# Microcontroller_board_Photodiode_plate.net
KiCad netlist of a schematic drawn in EasyEDA
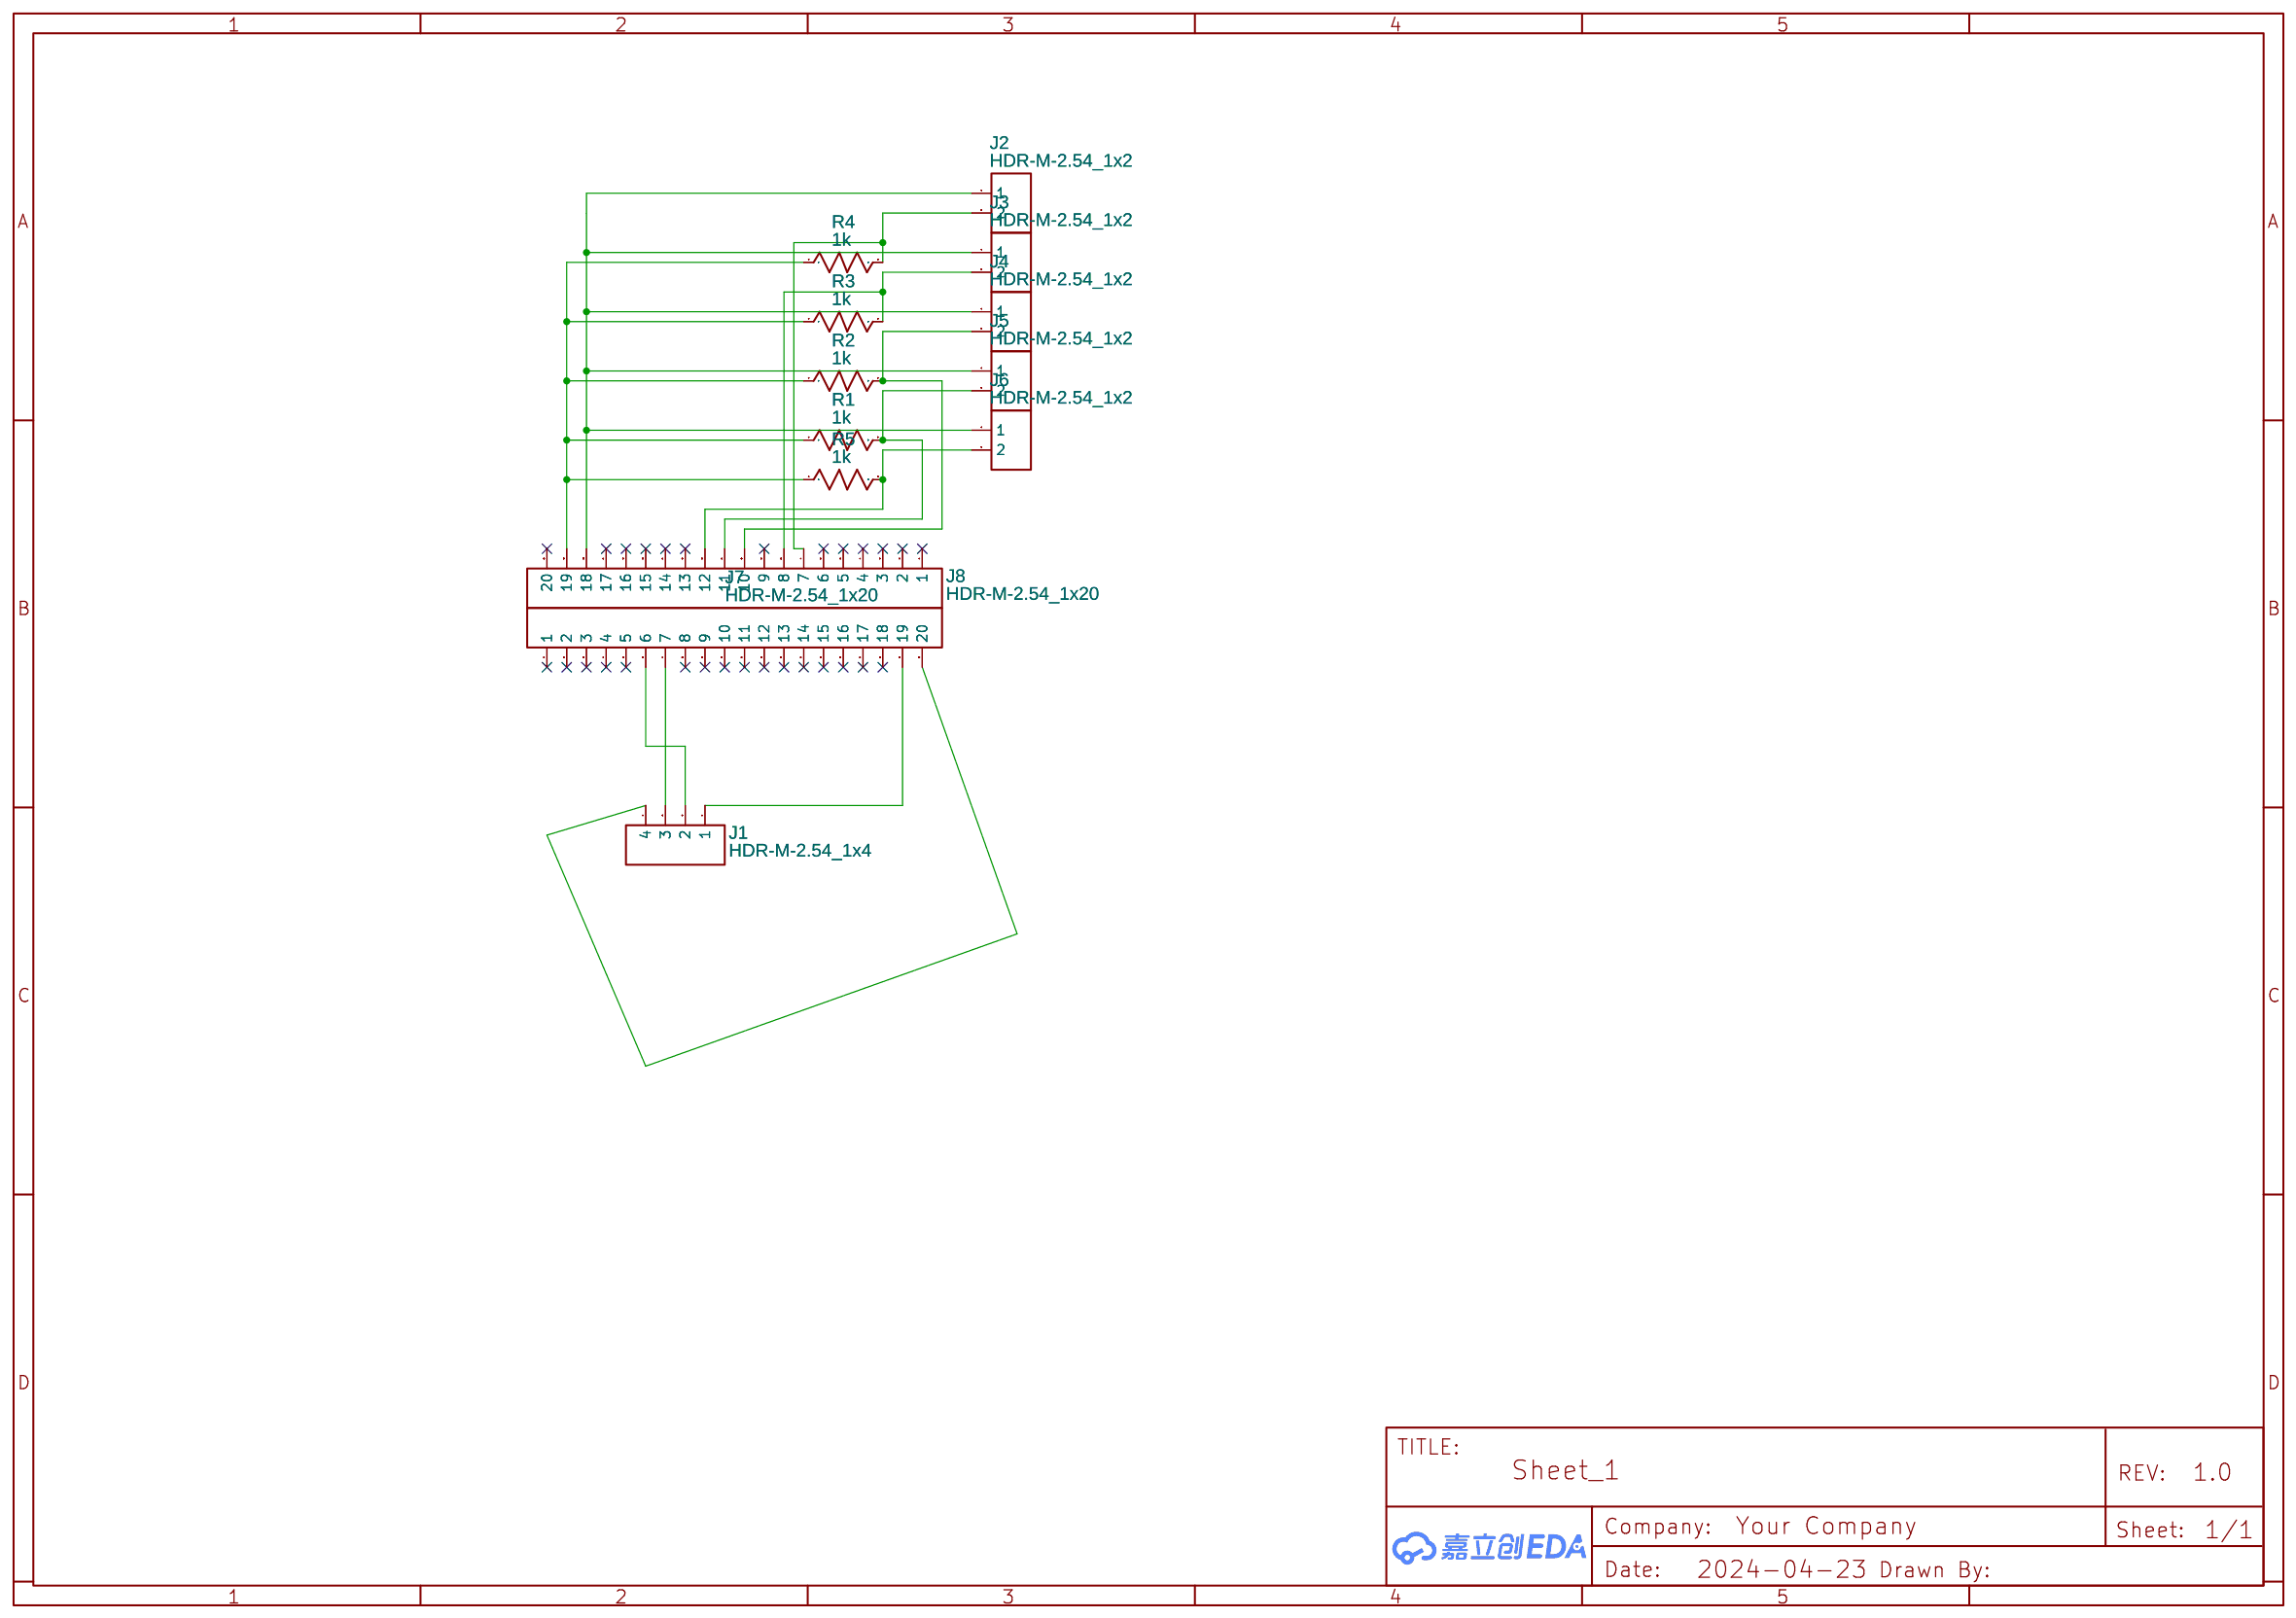
[diagram p0: schematic sheet]

(export (version "E")
  (design (tool "Eeschema 10.0.6"))
  (components
    (comp (ref "J1")
      (value "HDR-M-2.54_1x4")
      (fields (field (name "BOM_Supplier Part") "C124378"))
      (libsource (lib "") (part "HDR-M-2.54_1x4"))
    )
    (comp (ref "J2")
      (value "HDR-M-2.54_1x2")
      (fields (field (name "BOM_Supplier Part") "C124375"))
      (libsource (lib "") (part "HDR-M-2.54_1x2"))
    )
    (comp (ref "J3")
      (value "HDR-M-2.54_1x2")
      (fields (field (name "BOM_Supplier Part") "C124375"))
      (libsource (lib "") (part "HDR-M-2.54_1x2"))
    )
    (comp (ref "J4")
      (value "HDR-M-2.54_1x2")
      (fields (field (name "BOM_Supplier Part") "C124375"))
      (libsource (lib "") (part "HDR-M-2.54_1x2"))
    )
    (comp (ref "J5")
      (value "HDR-M-2.54_1x2")
      (fields (field (name "BOM_Supplier Part") "C124375"))
      (libsource (lib "") (part "HDR-M-2.54_1x2"))
    )
    (comp (ref "J6")
      (value "HDR-M-2.54_1x2")
      (fields (field (name "BOM_Supplier Part") "C124375"))
      (libsource (lib "") (part "HDR-M-2.54_1x2"))
    )
    (comp (ref "J7")
      (value "HDR-M-2.54_1x20")
      (fields (field (name "BOM_Supplier Part") "C50981"))
      (libsource (lib "") (part "HDR-M-2.54_1x20"))
    )
    (comp (ref "J8")
      (value "HDR-M-2.54_1x20")
      (fields (field (name "BOM_Supplier Part") "C50981"))
      (libsource (lib "") (part "HDR-M-2.54_1x20_1"))
    )
    (comp (ref "R1") (value "1k") (libsource (lib "") (part "R_AXIAL-0.4_US")))
    (comp (ref "R2") (value "1k") (libsource (lib "") (part "R_AXIAL-0.4_US")))
    (comp (ref "R3") (value "1k") (libsource (lib "") (part "R_AXIAL-0.4_US")))
    (comp (ref "R4") (value "1k") (libsource (lib "") (part "R_AXIAL-0.4_US")))
    (comp (ref "R5") (value "1k") (libsource (lib "") (part "R_AXIAL-0.4_US")))
  )
  (nets
    (net (code "1") (name "Net-(J1-Pad1)") (class "Default")
      (node (ref "J1") (pin "1") (pinfunction "1_1") (pintype "unspecified"))
      (node (ref "J7") (pin "19") (pinfunction "19_19") (pintype "unspecified"))
    )
    (net (code "2") (name "Net-(J1-Pad2)") (class "Default")
      (node (ref "J1") (pin "2") (pinfunction "2_2") (pintype "unspecified"))
      (node (ref "J7") (pin "6") (pinfunction "6_6") (pintype "unspecified"))
    )
    (net (code "3") (name "Net-(J1-Pad3)") (class "Default")
      (node (ref "J1") (pin "3") (pinfunction "3_3") (pintype "unspecified"))
      (node (ref "J7") (pin "7") (pinfunction "7_7") (pintype "unspecified"))
    )
    (net (code "4") (name "Net-(J1-Pad4)") (class "Default")
      (node (ref "J1") (pin "4") (pinfunction "4_4") (pintype "unspecified"))
      (node (ref "J7") (pin "20") (pinfunction "20_20") (pintype "unspecified"))
    )
    (net (code "5") (name "Net-(J2-Pad1)") (class "Default")
      (node (ref "J2") (pin "1") (pinfunction "1_1") (pintype "unspecified"))
      (node (ref "J3") (pin "1") (pinfunction "1_1") (pintype "unspecified"))
      (node (ref "J4") (pin "1") (pinfunction "1_1") (pintype "unspecified"))
      (node (ref "J5") (pin "1") (pinfunction "1_1") (pintype "unspecified"))
      (node (ref "J6") (pin "1") (pinfunction "1_1") (pintype "unspecified"))
      (node (ref "J8") (pin "18") (pinfunction "18_18") (pintype "unspecified"))
    )
    (net (code "6") (name "Net-(J2-Pad2)") (class "Default")
      (node (ref "J2") (pin "2") (pinfunction "2_2") (pintype "unspecified"))
      (node (ref "J8") (pin "7") (pinfunction "7_7") (pintype "unspecified"))
      (node (ref "R4") (pin "2") (pinfunction "2_2") (pintype "unspecified"))
    )
    (net (code "7") (name "Net-(J3-Pad2)") (class "Default")
      (node (ref "J3") (pin "2") (pinfunction "2_2") (pintype "unspecified"))
      (node (ref "J8") (pin "8") (pinfunction "8_8") (pintype "unspecified"))
      (node (ref "R3") (pin "2") (pinfunction "2_2") (pintype "unspecified"))
    )
    (net (code "8") (name "Net-(J4-Pad2)") (class "Default")
      (node (ref "J4") (pin "2") (pinfunction "2_2") (pintype "unspecified"))
      (node (ref "J8") (pin "10") (pinfunction "10_10") (pintype "unspecified"))
      (node (ref "R2") (pin "2") (pinfunction "2_2") (pintype "unspecified"))
    )
    (net (code "9") (name "Net-(J5-Pad2)") (class "Default")
      (node (ref "J5") (pin "2") (pinfunction "2_2") (pintype "unspecified"))
      (node (ref "J8") (pin "11") (pinfunction "11_11") (pintype "unspecified"))
      (node (ref "R1") (pin "2") (pinfunction "2_2") (pintype "unspecified"))
    )
    (net (code "10") (name "Net-(J6-Pad2)") (class "Default")
      (node (ref "J6") (pin "2") (pinfunction "2_2") (pintype "unspecified"))
      (node (ref "J8") (pin "12") (pinfunction "12_12") (pintype "unspecified"))
      (node (ref "R5") (pin "2") (pinfunction "2_2") (pintype "unspecified"))
    )
    (net (code "11") (name "Net-(J8-Pad19)") (class "Default")
      (node (ref "J8") (pin "19") (pinfunction "19_19") (pintype "unspecified"))
      (node (ref "R1") (pin "1") (pinfunction "1_1") (pintype "unspecified"))
      (node (ref "R2") (pin "1") (pinfunction "1_1") (pintype "unspecified"))
      (node (ref "R3") (pin "1") (pinfunction "1_1") (pintype "unspecified"))
      (node (ref "R4") (pin "1") (pinfunction "1_1") (pintype "unspecified"))
      (node (ref "R5") (pin "1") (pinfunction "1_1") (pintype "unspecified"))
    )
    (net (code "12") (name "unconnected-(J7-Pad1)") (class "Default")
      (node (ref "J7") (pin "1") (pinfunction "1_1") (pintype "unspecified+no_connect"))
    )
    (net (code "13") (name "unconnected-(J7-Pad2)") (class "Default")
      (node (ref "J7") (pin "2") (pinfunction "2_2") (pintype "unspecified+no_connect"))
    )
    (net (code "14") (name "unconnected-(J7-Pad3)") (class "Default")
      (node (ref "J7") (pin "3") (pinfunction "3_3") (pintype "unspecified+no_connect"))
    )
    (net (code "15") (name "unconnected-(J7-Pad4)") (class "Default")
      (node (ref "J7") (pin "4") (pinfunction "4_4") (pintype "unspecified+no_connect"))
    )
    (net (code "16") (name "unconnected-(J7-Pad5)") (class "Default")
      (node (ref "J7") (pin "5") (pinfunction "5_5") (pintype "unspecified+no_connect"))
    )
    (net (code "17") (name "unconnected-(J7-Pad8)") (class "Default")
      (node (ref "J7") (pin "8") (pinfunction "8_8") (pintype "unspecified+no_connect"))
    )
    (net (code "18") (name "unconnected-(J7-Pad9)") (class "Default")
      (node (ref "J7") (pin "9") (pinfunction "9_9") (pintype "unspecified+no_connect"))
    )
    (net (code "19") (name "unconnected-(J7-Pad10)") (class "Default")
      (node (ref "J7") (pin "10") (pinfunction "10_10") (pintype "unspecified+no_connect"))
    )
    (net (code "20") (name "unconnected-(J7-Pad11)") (class "Default")
      (node (ref "J7") (pin "11") (pinfunction "11_11") (pintype "unspecified+no_connect"))
    )
    (net (code "21") (name "unconnected-(J7-Pad12)") (class "Default")
      (node (ref "J7") (pin "12") (pinfunction "12_12") (pintype "unspecified+no_connect"))
    )
    (net (code "22") (name "unconnected-(J7-Pad13)") (class "Default")
      (node (ref "J7") (pin "13") (pinfunction "13_13") (pintype "unspecified+no_connect"))
    )
    (net (code "23") (name "unconnected-(J7-Pad14)") (class "Default")
      (node (ref "J7") (pin "14") (pinfunction "14_14") (pintype "unspecified+no_connect"))
    )
    (net (code "24") (name "unconnected-(J7-Pad15)") (class "Default")
      (node (ref "J7") (pin "15") (pinfunction "15_15") (pintype "unspecified+no_connect"))
    )
    (net (code "25") (name "unconnected-(J7-Pad16)") (class "Default")
      (node (ref "J7") (pin "16") (pinfunction "16_16") (pintype "unspecified+no_connect"))
    )
    (net (code "26") (name "unconnected-(J7-Pad17)") (class "Default")
      (node (ref "J7") (pin "17") (pinfunction "17_17") (pintype "unspecified+no_connect"))
    )
    (net (code "27") (name "unconnected-(J7-Pad18)") (class "Default")
      (node (ref "J7") (pin "18") (pinfunction "18_18") (pintype "unspecified+no_connect"))
    )
    (net (code "28") (name "unconnected-(J8-Pad1)") (class "Default")
      (node (ref "J8") (pin "1") (pinfunction "1_1") (pintype "unspecified+no_connect"))
    )
    (net (code "29") (name "unconnected-(J8-Pad2)") (class "Default")
      (node (ref "J8") (pin "2") (pinfunction "2_2") (pintype "unspecified+no_connect"))
    )
    (net (code "30") (name "unconnected-(J8-Pad3)") (class "Default")
      (node (ref "J8") (pin "3") (pinfunction "3_3") (pintype "unspecified+no_connect"))
    )
    (net (code "31") (name "unconnected-(J8-Pad4)") (class "Default")
      (node (ref "J8") (pin "4") (pinfunction "4_4") (pintype "unspecified+no_connect"))
    )
    (net (code "32") (name "unconnected-(J8-Pad5)") (class "Default")
      (node (ref "J8") (pin "5") (pinfunction "5_5") (pintype "unspecified+no_connect"))
    )
    (net (code "33") (name "unconnected-(J8-Pad6)") (class "Default")
      (node (ref "J8") (pin "6") (pinfunction "6_6") (pintype "unspecified+no_connect"))
    )
    (net (code "34") (name "unconnected-(J8-Pad9)") (class "Default")
      (node (ref "J8") (pin "9") (pinfunction "9_9") (pintype "unspecified+no_connect"))
    )
    (net (code "35") (name "unconnected-(J8-Pad13)") (class "Default")
      (node (ref "J8") (pin "13") (pinfunction "13_13") (pintype "unspecified+no_connect"))
    )
    (net (code "36") (name "unconnected-(J8-Pad14)") (class "Default")
      (node (ref "J8") (pin "14") (pinfunction "14_14") (pintype "unspecified+no_connect"))
    )
    (net (code "37") (name "unconnected-(J8-Pad15)") (class "Default")
      (node (ref "J8") (pin "15") (pinfunction "15_15") (pintype "unspecified+no_connect"))
    )
    (net (code "38") (name "unconnected-(J8-Pad16)") (class "Default")
      (node (ref "J8") (pin "16") (pinfunction "16_16") (pintype "unspecified+no_connect"))
    )
    (net (code "39") (name "unconnected-(J8-Pad17)") (class "Default")
      (node (ref "J8") (pin "17") (pinfunction "17_17") (pintype "unspecified+no_connect"))
    )
    (net (code "40") (name "unconnected-(J8-Pad20)") (class "Default")
      (node (ref "J8") (pin "20") (pinfunction "20_20") (pintype "unspecified+no_connect"))
    )
  )
)
